# utilidong-lipo-charger-mk-1_0.net
KiCad netlist of a schematic drawn in EAGLE
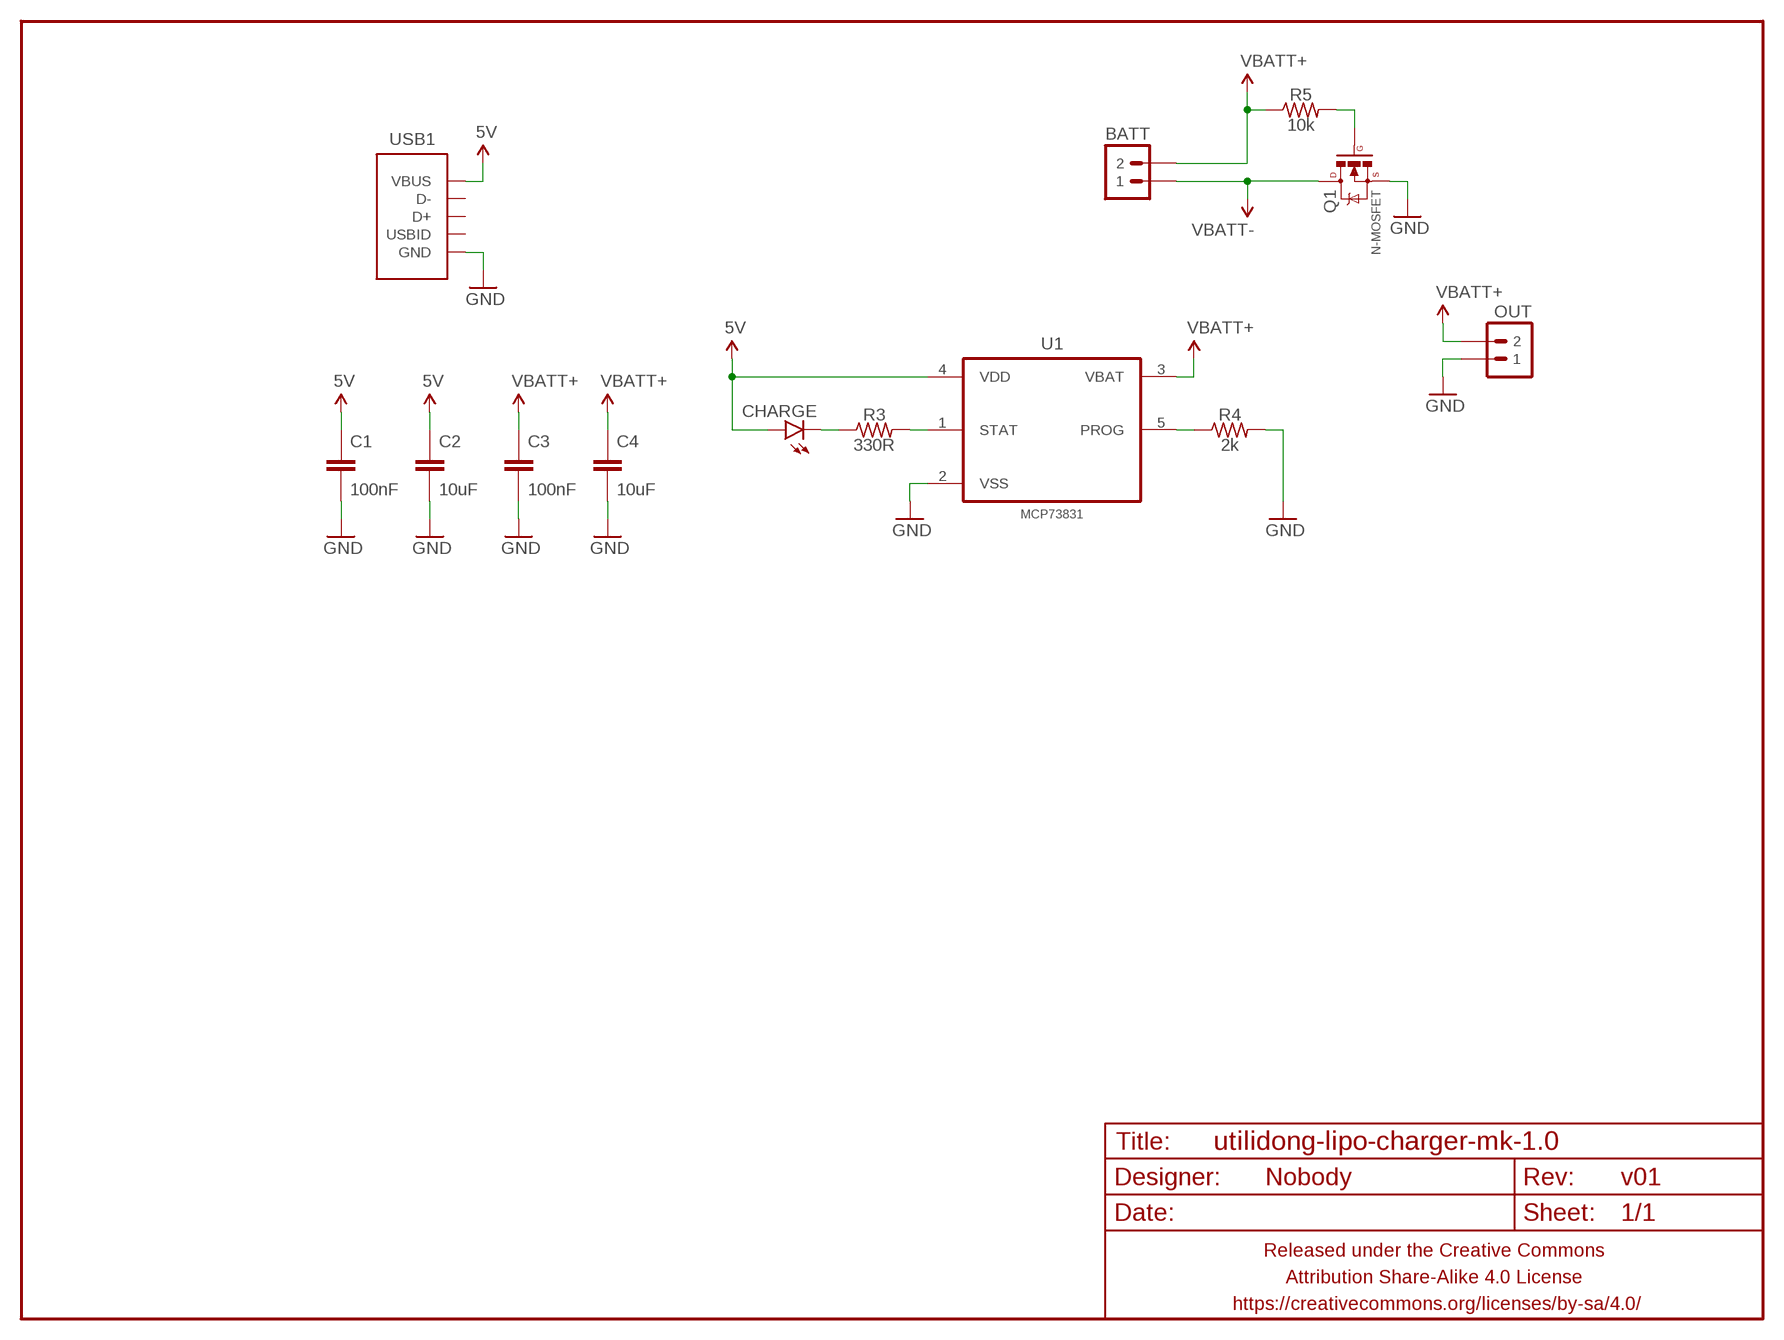
[diagram p0: schematic, sheet 1]

(export (version "E")
  (design (tool "Eeschema 10.0.6"))
  (components
    (comp (ref "BATT")
      (value "M02PTH-CENTERED-R+")
      (footprint "eagle-import:1X02-CENTER-R+")
      (libsource (lib "eagle-import") (part "M02PTH-CENTERED-R+"))
    )
    (comp (ref "C1")
      (value "100nF")
      (footprint "eagle-import:C0805")
      (libsource (lib "eagle-import") (part "CAPACITOR-CERAMICC0805"))
    )
    (comp (ref "C2")
      (value "10uF")
      (footprint "eagle-import:C1206")
      (libsource (lib "eagle-import") (part "CAPACITOR-CERAMICC1206"))
    )
    (comp (ref "C3")
      (value "100nF")
      (footprint "eagle-import:C0805")
      (libsource (lib "eagle-import") (part "CAPACITOR-CERAMICC0805"))
    )
    (comp (ref "C4")
      (value "10uF")
      (footprint "eagle-import:C1206")
      (libsource (lib "eagle-import") (part "CAPACITOR-CERAMICC1206"))
    )
    (comp (ref "CHARGE")
      (value "LED1206")
      (footprint "eagle-import:LED-1206")
      (libsource (lib "eagle-import") (part "LED1206"))
    )
    (comp (ref "FRAME1")
      (value "FRAME-LETTERNO_PACKAGE")
      (footprint "eagle-import:DUMMY")
      (fields (field (name "DESIGNER") "Nobody"))
      (libsource (lib "eagle-import") (part "FRAME-LETTERNO_PACKAGE"))
    )
    (comp (ref "OUT")
      (value "M02PTH-CENTERED-R+")
      (footprint "eagle-import:1X02-CENTER-R+")
      (libsource (lib "eagle-import") (part "M02PTH-CENTERED-R+"))
    )
    (comp (ref "Q1")
      (value "N-MOSFET")
      (footprint "eagle-import:SOT23")
      (libsource (lib "eagle-import") (part "MOSFET-NCHANNELBSS138"))
    )
    (comp (ref "R3")
      (value "330R")
      (footprint "eagle-import:R0805")
      (libsource (lib "eagle-import") (part "RESISTORR0805"))
    )
    (comp (ref "R4")
      (value "2k")
      (footprint "eagle-import:R0805")
      (libsource (lib "eagle-import") (part "RESISTORR0805"))
    )
    (comp (ref "R5")
      (value "10k")
      (footprint "eagle-import:R0805")
      (libsource (lib "eagle-import") (part "RESISTORR0805"))
    )
    (comp (ref "U1")
      (value "MCP73831")
      (footprint "eagle-import:SOT95P280X145-5N")
      (fields (field (name "MPN") "MCP73831T-2ACI/OT"))
      (libsource (lib "eagle-import") (part "MCP73831T-2ACI/OT"))
    )
    (comp (ref "USB1")
      (value "USB-ABCOMBO")
      (footprint "eagle-import:USB-MICRO-B-FCI-CUTOUT")
      (libsource (lib "eagle-import") (part "USB-ABCOMBO"))
    )
  )
  (nets
    (net (code "1") (name "5V") (class "Default")
      (node (ref "C1") (pin "1") (pinfunction "1_1") (pintype "passive"))
      (node (ref "C2") (pin "1") (pinfunction "1_1") (pintype "passive"))
      (node (ref "CHARGE") (pin "A") (pinfunction "A_A") (pintype "passive"))
      (node (ref "U1") (pin "4") (pinfunction "VDD_4") (pintype "power_in"))
      (node (ref "USB1") (pin "1") (pinfunction "VBUS_1") (pintype "bidirectional"))
    )
    (net (code "2") (name "GND") (class "Default")
      (node (ref "C1") (pin "2") (pinfunction "2_2") (pintype "passive"))
      (node (ref "C2") (pin "2") (pinfunction "2_2") (pintype "passive"))
      (node (ref "C3") (pin "2") (pinfunction "2_2") (pintype "passive"))
      (node (ref "C4") (pin "2") (pinfunction "2_2") (pintype "passive"))
      (node (ref "OUT") (pin "1") (pinfunction "1_1") (pintype "passive"))
      (node (ref "Q1") (pin "2") (pinfunction "S_2") (pintype "passive"))
      (node (ref "R4") (pin "2") (pinfunction "2_2") (pintype "passive"))
      (node (ref "U1") (pin "2") (pinfunction "VSS_2") (pintype "power_in"))
      (node (ref "USB1") (pin "5") (pinfunction "GND_5") (pintype "bidirectional"))
      (node (ref "USB1") (pin "P$1") (pinfunction "GND_P$1") (pintype "bidirectional"))
      (node (ref "USB1") (pin "P$2") (pinfunction "GND_P$2") (pintype "bidirectional"))
    )
    (net (code "3") (name "Net-(CHARGE-PadC)") (class "Default")
      (node (ref "CHARGE") (pin "C") (pinfunction "C_C") (pintype "passive"))
      (node (ref "R3") (pin "1") (pinfunction "1_1") (pintype "passive"))
    )
    (net (code "4") (name "Net-(Q1-G)") (class "Default")
      (node (ref "Q1") (pin "1") (pinfunction "G_1") (pintype "passive"))
      (node (ref "R5") (pin "2") (pinfunction "2_2") (pintype "passive"))
    )
    (net (code "5") (name "Net-(U1-PROG)") (class "Default")
      (node (ref "R4") (pin "1") (pinfunction "1_1") (pintype "passive"))
      (node (ref "U1") (pin "5") (pinfunction "PROG_5") (pintype "input"))
    )
    (net (code "6") (name "Net-(U1-STAT)") (class "Default")
      (node (ref "R3") (pin "2") (pinfunction "2_2") (pintype "passive"))
      (node (ref "U1") (pin "1") (pinfunction "STAT_1") (pintype "output"))
    )
    (net (code "7") (name "VBATT+") (class "Default")
      (node (ref "BATT") (pin "2") (pinfunction "2_2") (pintype "passive"))
      (node (ref "C3") (pin "1") (pinfunction "1_1") (pintype "passive"))
      (node (ref "C4") (pin "1") (pinfunction "1_1") (pintype "passive"))
      (node (ref "OUT") (pin "2") (pinfunction "2_2") (pintype "passive"))
      (node (ref "R5") (pin "1") (pinfunction "1_1") (pintype "passive"))
      (node (ref "U1") (pin "3") (pinfunction "VBAT_3") (pintype "output"))
    )
    (net (code "8") (name "VBATT-") (class "Default")
      (node (ref "BATT") (pin "1") (pinfunction "1_1") (pintype "passive"))
      (node (ref "Q1") (pin "3") (pinfunction "D_3") (pintype "passive"))
    )
    (net (code "9") (name "unconnected-(USB1-D+-Pad3)") (class "Default")
      (node (ref "USB1") (pin "3") (pinfunction "D+_3") (pintype "bidirectional"))
    )
    (net (code "10") (name "unconnected-(USB1-D--Pad2)") (class "Default")
      (node (ref "USB1") (pin "2") (pinfunction "D-_2") (pintype "bidirectional"))
    )
    (net (code "11") (name "unconnected-(USB1-USBID-Pad4)") (class "Default")
      (node (ref "USB1") (pin "4") (pinfunction "USBID_4") (pintype "bidirectional"))
    )
  )
)
